# Auxilary.net
KiCad netlist of a schematic drawn in Altium Designer
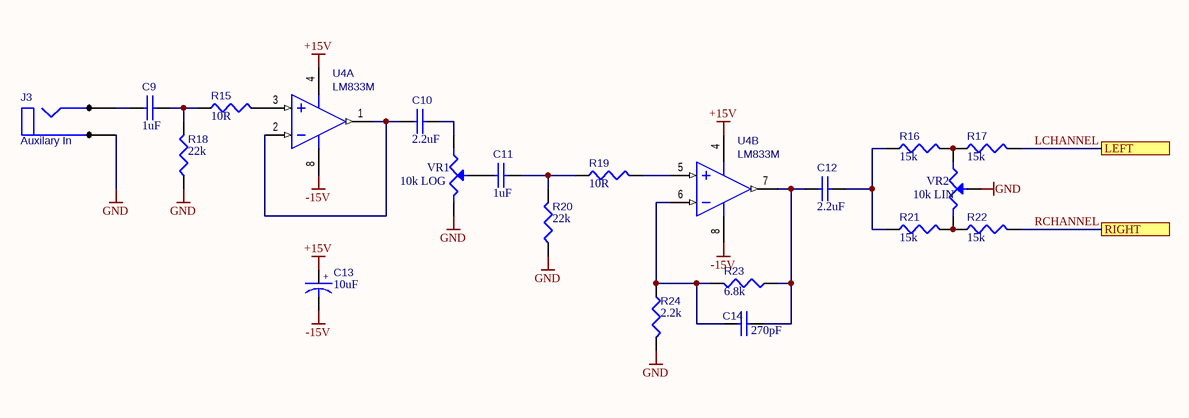
[diagram p0: Auxilary.SchDoc]

(export (version "E")
  (design (tool "Eeschema 10.0.6"))
  (components
    (comp (ref "C9")
      (value "1uF")
      (footprint "RB.2/.4-NP")
      (description "Capacitor")
      (libsource (lib "*") (part "CAP"))
    )
    (comp (ref "C10")
      (value "2.2uF")
      (footprint "RB.2/.4-NP")
      (description "Capacitor")
      (libsource (lib "*") (part "CAP"))
    )
    (comp (ref "C11")
      (value "1uF")
      (footprint "RB.2/.4-NP")
      (description "Capacitor")
      (libsource (lib "*") (part "CAP"))
    )
    (comp (ref "C12")
      (value "2.2uF")
      (footprint "RB.2/.4-NP")
      (description "Capacitor")
      (libsource (lib "*") (part "CAP"))
    )
    (comp (ref "C13")
      (value "10uF")
      (footprint "RB.2/.4")
      (description "Bi-Polar Capacitor")
      (libsource (lib "*") (part "CAPACITOR POL"))
    )
    (comp (ref "C14")
      (value "270pF")
      (footprint "RAD0.2")
      (description "Capacitor")
      (libsource (lib "*") (part "CAP"))
    )
    (comp (ref "J3")
      (value "Auxilary In")
      (footprint "JACK-6.25MM")
      (libsource (lib "*") (part "PHONEJACK MONO"))
    )
    (comp (ref "R15")
      (value "10R")
      (footprint "AXIAL0.4")
      (description "Resistor")
      (libsource (lib "*") (part "RES1"))
    )
    (comp (ref "R16")
      (value "15k")
      (footprint "AXIAL0.4")
      (description "Resistor")
      (libsource (lib "*") (part "RES1"))
    )
    (comp (ref "R17")
      (value "15k")
      (footprint "AXIAL0.4")
      (description "Resistor")
      (libsource (lib "*") (part "RES1"))
    )
    (comp (ref "R18")
      (value "22k")
      (footprint "AXIAL0.4")
      (description "Resistor")
      (libsource (lib "") (part "RES1_2"))
    )
    (comp (ref "R19")
      (value "10R")
      (footprint "AXIAL0.4")
      (description "Resistor")
      (libsource (lib "*") (part "RES1"))
    )
    (comp (ref "R20")
      (value "22k")
      (footprint "AXIAL0.4")
      (description "Resistor")
      (libsource (lib "") (part "RES1_2"))
    )
    (comp (ref "R21")
      (value "15k")
      (footprint "AXIAL0.4")
      (description "Resistor")
      (libsource (lib "*") (part "RES1"))
    )
    (comp (ref "R22")
      (value "15k")
      (footprint "AXIAL0.4")
      (description "Resistor")
      (libsource (lib "*") (part "RES1"))
    )
    (comp (ref "R23")
      (value "6.8k")
      (footprint "AXIAL0.4")
      (description "Resistor")
      (libsource (lib "") (part "RES1_1"))
    )
    (comp (ref "R24")
      (value "2.2k")
      (footprint "AXIAL0.4")
      (description "Resistor")
      (libsource (lib "") (part "RES1_3"))
    )
    (comp (ref "U4")
      (value "LM833M")
      (footprint "DIP8")
      (description "Fast Settling Dual Operational Amplifier")
      (libsource (lib "*") (part "LM833M"))
    )
    (comp (ref "VR1")
      (value "10k LOG")
      (footprint "POT - 24MM")
      (description "Potentiometer")
      (libsource (lib "*") (part "POT1"))
    )
    (comp (ref "VR2")
      (value "10k LIN")
      (footprint "POT - 24MM")
      (description "Potentiometer")
      (libsource (lib "*") (part "POT1"))
    )
  )
  (nets
    (net (code "1") (name "+15V") (class "Default")
      (node (ref "C13") (pin "1") (pinfunction "1_1") (pintype "passive"))
      (node (ref "U4") (pin "4") (pinfunction "V-_4") (pintype "power_in"))
    )
    (net (code "2") (name "-15V") (class "Default")
      (node (ref "C13") (pin "2") (pinfunction "2_2") (pintype "passive"))
      (node (ref "U4") (pin "8") (pinfunction "V+_8") (pintype "power_in"))
    )
    (net (code "3") (name "/LCHANNEL") (class "Default")
      (node (ref "R17") (pin "2") (pinfunction "2_2") (pintype "passive"))
    )
    (net (code "4") (name "/RCHANNEL") (class "Default")
      (node (ref "R22") (pin "2") (pinfunction "2_2") (pintype "passive"))
    )
    (net (code "5") (name "GND") (class "Default")
      (node (ref "J3") (pin "3") (pinfunction "C_3") (pintype "passive"))
      (node (ref "R18") (pin "1") (pinfunction "1_1") (pintype "passive"))
      (node (ref "R20") (pin "1") (pinfunction "1_1") (pintype "passive"))
      (node (ref "R24") (pin "2") (pinfunction "2_2") (pintype "passive"))
      (node (ref "VR1") (pin "3") (pinfunction "3_3") (pintype "passive"))
      (node (ref "VR2") (pin "2") (pinfunction "W_2") (pintype "passive"))
    )
    (net (code "6") (name "Net-(C9-Pad2)") (class "Default")
      (node (ref "C9") (pin "2") (pinfunction "2_2") (pintype "passive"))
      (node (ref "R15") (pin "1") (pinfunction "1_1") (pintype "passive"))
      (node (ref "R18") (pin "2") (pinfunction "2_2") (pintype "passive"))
    )
    (net (code "7") (name "Net-(C10-Pad2)") (class "Default")
      (node (ref "C10") (pin "2") (pinfunction "2_2") (pintype "passive"))
      (node (ref "VR1") (pin "1") (pinfunction "1_1") (pintype "passive"))
    )
    (net (code "8") (name "Net-(C11-Pad2)") (class "Default")
      (node (ref "C11") (pin "2") (pinfunction "2_2") (pintype "passive"))
      (node (ref "R19") (pin "1") (pinfunction "1_1") (pintype "passive"))
      (node (ref "R20") (pin "2") (pinfunction "2_2") (pintype "passive"))
    )
    (net (code "9") (name "Net-(C12-Pad2)") (class "Default")
      (node (ref "C12") (pin "2") (pinfunction "2_2") (pintype "passive"))
      (node (ref "R16") (pin "1") (pinfunction "1_1") (pintype "passive"))
      (node (ref "R21") (pin "1") (pinfunction "1_1") (pintype "passive"))
    )
    (net (code "10") (name "Net-(J3-A)") (class "Default")
      (node (ref "C9") (pin "1") (pinfunction "1_1") (pintype "passive"))
      (node (ref "J3") (pin "1") (pinfunction "A_1") (pintype "passive"))
    )
    (net (code "11") (name "Net-(R16-Pad2)") (class "Default")
      (node (ref "R16") (pin "2") (pinfunction "2_2") (pintype "passive"))
      (node (ref "R17") (pin "1") (pinfunction "1_1") (pintype "passive"))
      (node (ref "VR2") (pin "1") (pinfunction "1_1") (pintype "passive"))
    )
    (net (code "12") (name "Net-(R21-Pad2)") (class "Default")
      (node (ref "R21") (pin "2") (pinfunction "2_2") (pintype "passive"))
      (node (ref "R22") (pin "1") (pinfunction "1_1") (pintype "passive"))
      (node (ref "VR2") (pin "3") (pinfunction "3_3") (pintype "passive"))
    )
    (net (code "13") (name "Net-(U4A-IN1+)") (class "Default")
      (node (ref "R15") (pin "2") (pinfunction "2_2") (pintype "passive"))
      (node (ref "U4") (pin "3") (pinfunction "IN1+_3") (pintype "input"))
    )
    (net (code "14") (name "Net-(U4A-IN1-)") (class "Default")
      (node (ref "C10") (pin "1") (pinfunction "1_1") (pintype "passive"))
      (node (ref "U4") (pin "1") (pinfunction "OUT1_1") (pintype "output"))
      (node (ref "U4") (pin "2") (pinfunction "IN1-_2") (pintype "input"))
    )
    (net (code "15") (name "Net-(U4B-IN2+)") (class "Default")
      (node (ref "R19") (pin "2") (pinfunction "2_2") (pintype "passive"))
      (node (ref "U4") (pin "5") (pinfunction "IN2+_5") (pintype "input"))
    )
    (net (code "16") (name "Net-(U4B-IN2-)") (class "Default")
      (node (ref "C14") (pin "1") (pinfunction "1_1") (pintype "passive"))
      (node (ref "R23") (pin "2") (pinfunction "2_2") (pintype "passive"))
      (node (ref "R24") (pin "1") (pinfunction "1_1") (pintype "passive"))
      (node (ref "U4") (pin "6") (pinfunction "IN2-_6") (pintype "input"))
    )
    (net (code "17") (name "Net-(U4B-OUT2)") (class "Default")
      (node (ref "C12") (pin "1") (pinfunction "1_1") (pintype "passive"))
      (node (ref "C14") (pin "2") (pinfunction "2_2") (pintype "passive"))
      (node (ref "R23") (pin "1") (pinfunction "1_1") (pintype "passive"))
      (node (ref "U4") (pin "7") (pinfunction "OUT2_7") (pintype "output"))
    )
    (net (code "18") (name "Net-(VR1-W)") (class "Default")
      (node (ref "C11") (pin "1") (pinfunction "1_1") (pintype "passive"))
      (node (ref "VR1") (pin "2") (pinfunction "W_2") (pintype "passive"))
    )
  )
)
